# COMM.net
KiCad netlist of a schematic drawn in Altium Designer
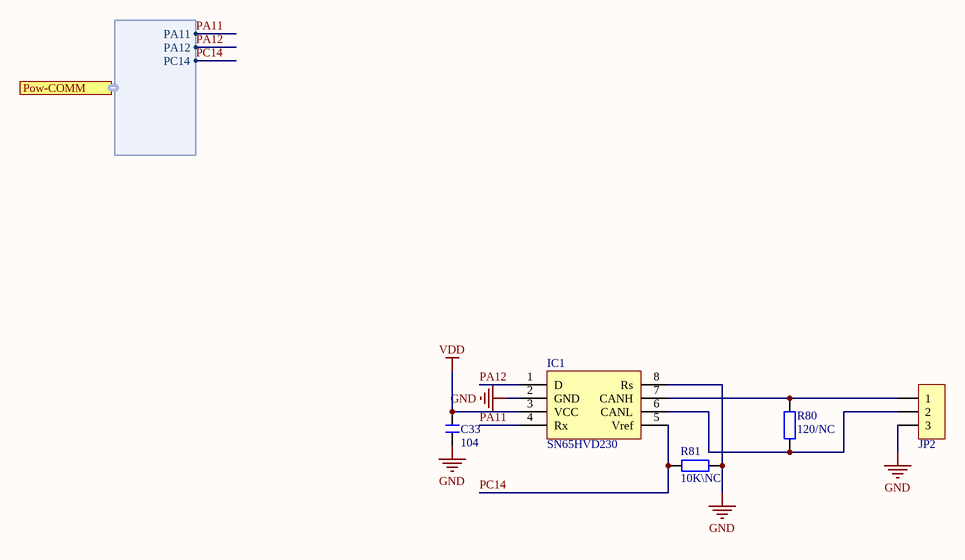
[diagram p0: COMM.SchDoc]

(export (version "E")
  (design (tool "Eeschema 10.0.6"))
  (components
    (comp (ref "C33")
      (value "104")
      (footprint "C 0603_L")
      (description "无极性贴片电容")
      (fields (field (name "版权归属") "源创客"))
      (libsource (lib "3.1   - 电阻-电容-电感") (part "C"))
    )
    (comp (ref "IC1")
      (value "SN65HVD230")
      (footprint "SOP8_N")
      (description "CAN芯片")
      (fields (field (name "版权归属") "源创客"))
      (libsource (lib "1.1   - IC芯片") (part "SN65HVD230"))
    )
    (comp (ref "JP2")
      (value "HDR-1X3")
      (footprint "XH2.54-WI-3P")
      (description "3P接插件")
      (fields (field (name "版权归属") "源创客"))
      (libsource (lib "4.5   - 接插件-脚距2.54") (part "Header 3"))
    )
    (comp (ref "R80")
      (value "120/NC")
      (footprint "R 1206_L")
      (description "贴片电阻")
      (fields (field (name "版权归属") "源创客"))
      (libsource (lib "3.1   - 电阻-电容-电感") (part "R"))
    )
    (comp (ref "R81")
      (value "10~{K}NC")
      (footprint "R 0603_L")
      (description "贴片电阻")
      (fields (field (name "版权归属") "源创客"))
      (libsource (lib "3.1   - 电阻-电容-电感") (part "R"))
    )
  )
  (nets
    (net (code "2") (name "/PA11") (class "Default")
      (node (ref "IC1") (pin "4") (pinfunction "Rx_4") (pintype "passive"))
    )
    (net (code "3") (name "/PA12") (class "Default")
      (node (ref "IC1") (pin "1") (pinfunction "D_1") (pintype "passive"))
    )
    (net (code "4") (name "/PC14") (class "Default")
      (node (ref "IC1") (pin "5") (pinfunction "Vref_5") (pintype "passive"))
      (node (ref "R81") (pin "1") (pinfunction "1_1") (pintype "passive"))
    )
    (net (code "6") (name "GND") (class "Default")
      (node (ref "C33") (pin "2") (pinfunction "2_2") (pintype "passive"))
      (node (ref "IC1") (pin "2") (pinfunction "GND_2") (pintype "passive"))
      (node (ref "IC1") (pin "8") (pinfunction "Rs_8") (pintype "passive"))
      (node (ref "JP2") (pin "3") (pinfunction "3_3") (pintype "passive"))
      (node (ref "R81") (pin "2") (pinfunction "2_2") (pintype "passive"))
    )
    (net (code "7") (name "Net-(IC1-CANH)") (class "Default")
      (node (ref "IC1") (pin "7") (pinfunction "CANH_7") (pintype "passive"))
      (node (ref "JP2") (pin "1") (pinfunction "1_1") (pintype "passive"))
      (node (ref "R80") (pin "2") (pinfunction "2_2") (pintype "passive"))
    )
    (net (code "8") (name "Net-(IC1-CANL)") (class "Default")
      (node (ref "IC1") (pin "6") (pinfunction "CANL_6") (pintype "passive"))
      (node (ref "JP2") (pin "2") (pinfunction "2_2") (pintype "passive"))
      (node (ref "R80") (pin "1") (pinfunction "1_1") (pintype "passive"))
    )
    (net (code "9") (name "VDD") (class "Default")
      (node (ref "C33") (pin "1") (pinfunction "1_1") (pintype "passive"))
      (node (ref "IC1") (pin "3") (pinfunction "VCC_3") (pintype "passive"))
    )
  )
)
